# HV.net
KiCad netlist of a schematic drawn in Altium Designer
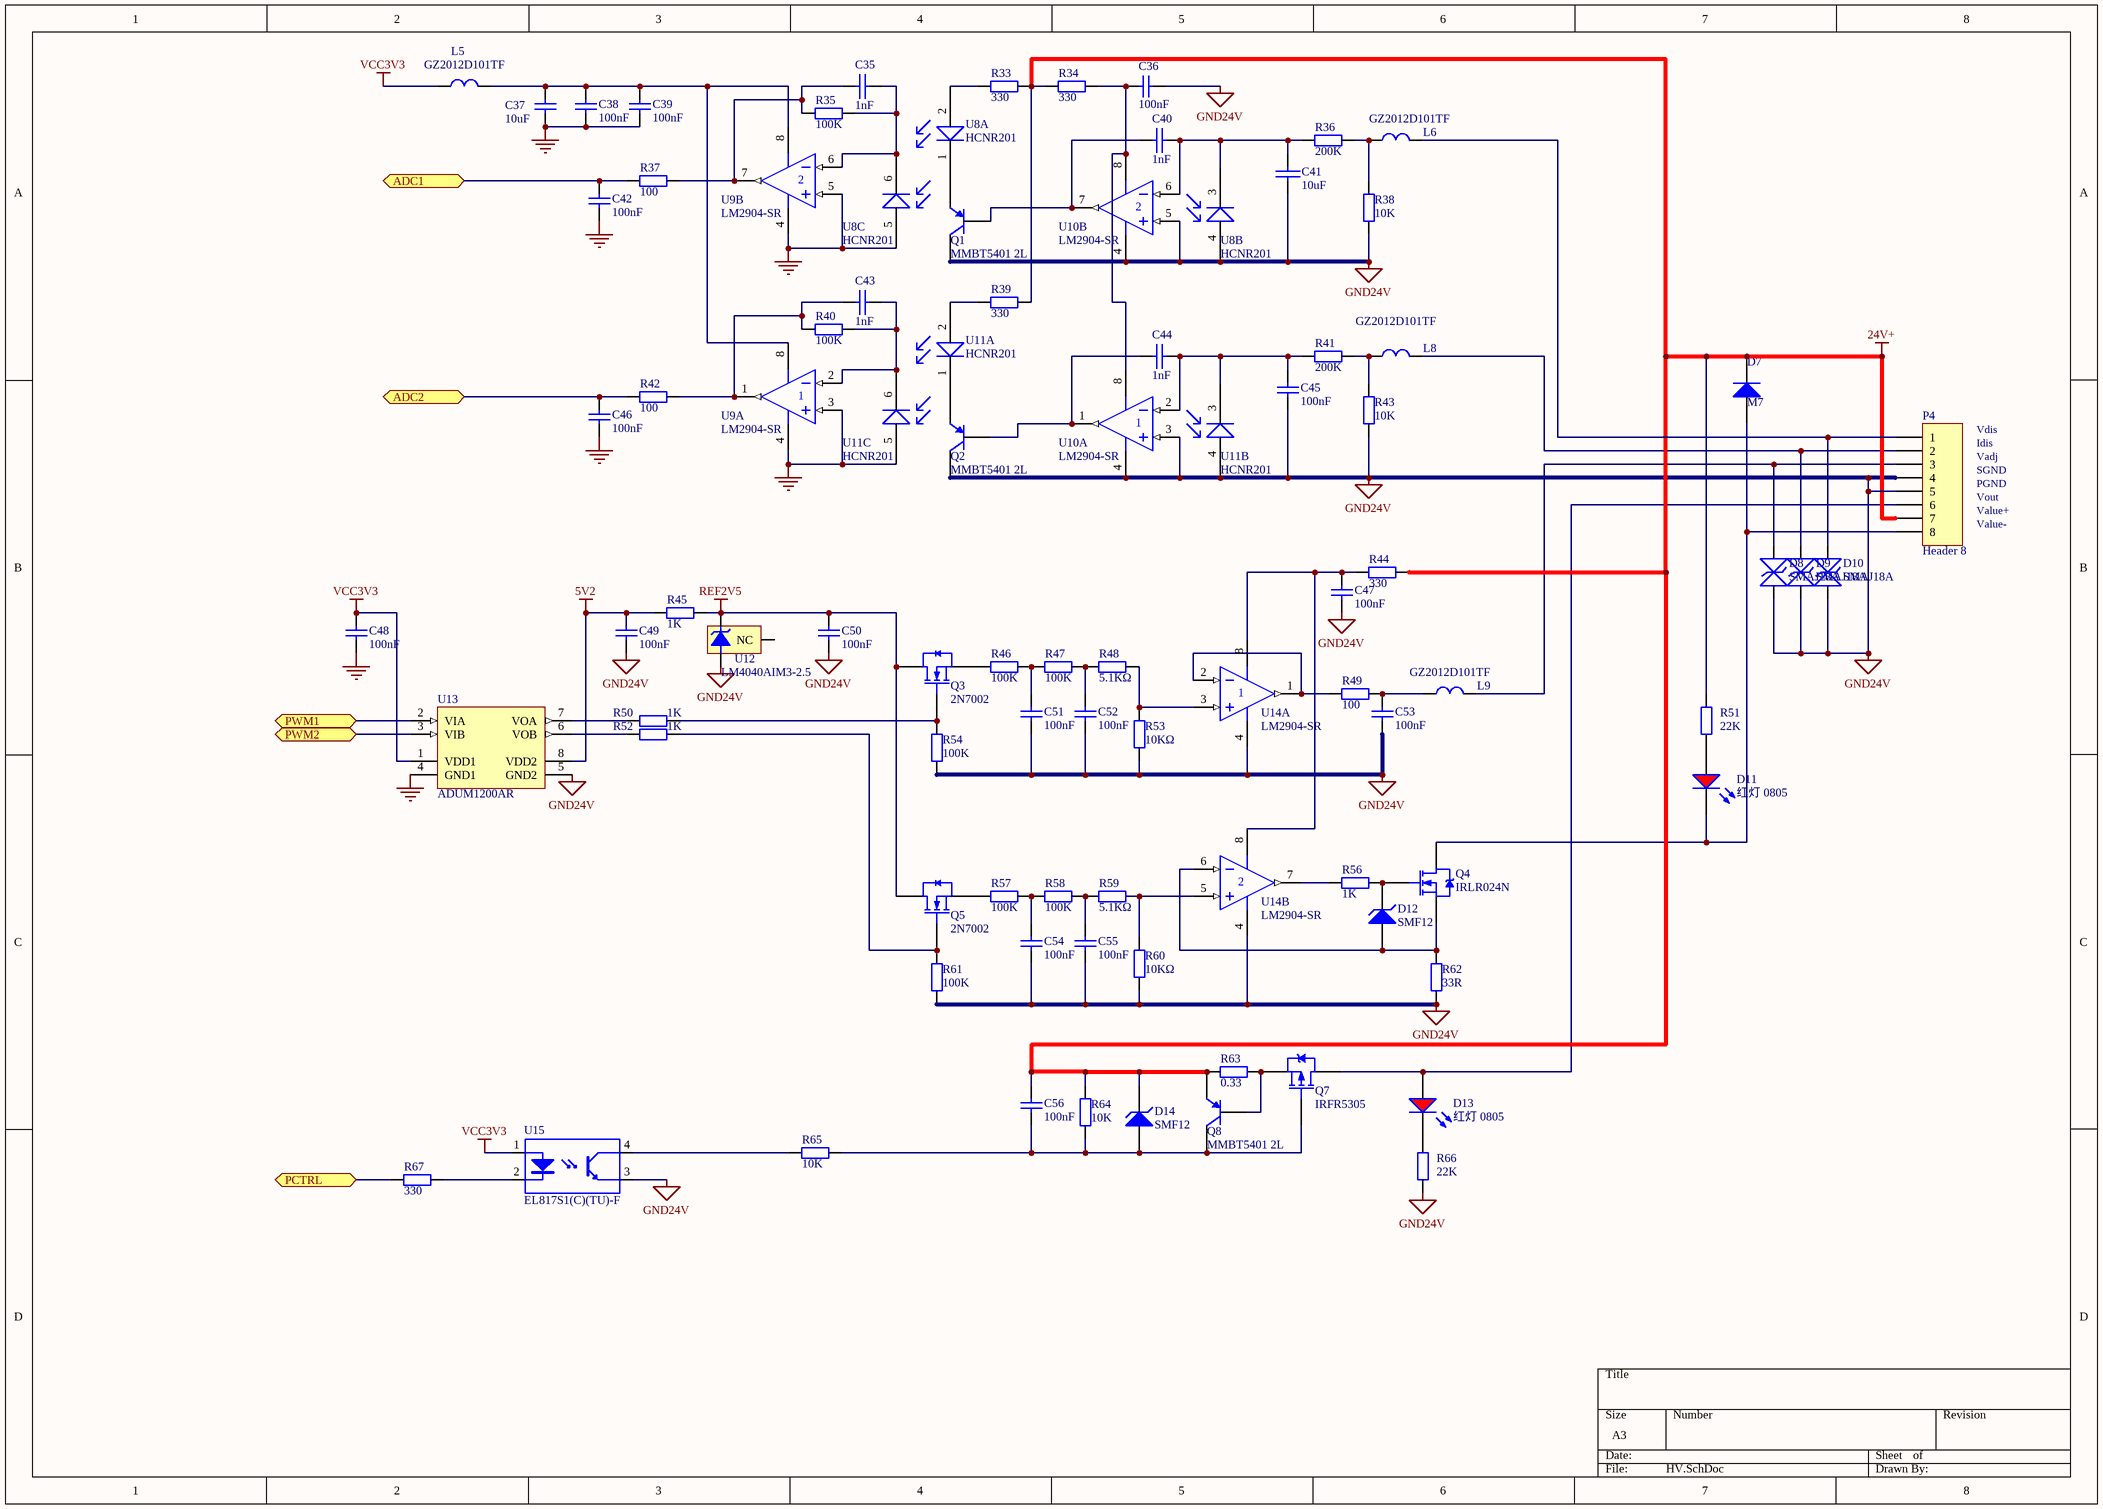
[diagram p0: HV.SchDoc]

(export (version "E")
  (design (tool "Eeschema 10.0.6"))
  (components
    (comp (ref "C35")
      (value "1nF")
      (footprint "0805_C")
      (description "Capacitor")
      (libsource (lib "*") (part "CAP"))
    )
    (comp (ref "C36")
      (value "100nF")
      (footprint "0805_C")
      (description "贴片电容")
      (libsource (lib "Miscellaneous Devices LC") (part "0805 100nF(104) 10% 50V"))
    )
    (comp (ref "C37")
      (value "10uF")
      (footprint "0805_C")
      (description "贴片电容")
      (libsource (lib "Miscellaneous Devices LC") (part "1206 10uF (106) 10% 50V"))
    )
    (comp (ref "C38")
      (value "100nF")
      (footprint "0805_C")
      (description "贴片电容")
      (libsource (lib "Miscellaneous Devices LC") (part "0805 100nF(104) 10% 50V"))
    )
    (comp (ref "C39")
      (value "100nF")
      (footprint "0805_C")
      (description "贴片电容")
      (libsource (lib "Miscellaneous Devices LC") (part "0805 100nF(104) 10% 50V"))
    )
    (comp (ref "C40")
      (value "1nF")
      (footprint "0805_C")
      (description "Capacitor")
      (libsource (lib "*") (part "CAP"))
    )
    (comp (ref "C41")
      (value "10uF")
      (footprint "0805_C")
      (description "Capacitor")
      (libsource (lib "*") (part "CC"))
    )
    (comp (ref "C42")
      (value "100nF")
      (footprint "0805_C")
      (description "贴片电容")
      (libsource (lib "Miscellaneous Devices LC") (part "0805 100nF(104) 10% 50V"))
    )
    (comp (ref "C43")
      (value "1nF")
      (footprint "0805_C")
      (description "Capacitor")
      (libsource (lib "*") (part "CAP"))
    )
    (comp (ref "C44")
      (value "1nF")
      (footprint "0805_C")
      (description "Capacitor")
      (libsource (lib "*") (part "CAP"))
    )
    (comp (ref "C45")
      (value "100nF")
      (footprint "0805_C")
      (description "贴片电容")
      (libsource (lib "Miscellaneous Devices LC") (part "0805 100nF(104) 10% 50V"))
    )
    (comp (ref "C46")
      (value "100nF")
      (footprint "0805_C")
      (description "贴片电容")
      (libsource (lib "Miscellaneous Devices LC") (part "0805 100nF(104) 10% 50V"))
    )
    (comp (ref "C47")
      (value "100nF")
      (footprint "0805_C")
      (description "贴片电容")
      (libsource (lib "Miscellaneous Devices LC") (part "0805 100nF(104) 10% 50V"))
    )
    (comp (ref "C48")
      (value "100nF")
      (footprint "0805_C")
      (description "贴片电容")
      (libsource (lib "Miscellaneous Devices LC") (part "0805 100nF(104) 10% 50V"))
    )
    (comp (ref "C49")
      (value "100nF")
      (footprint "0805_C")
      (description "贴片电容")
      (libsource (lib "Miscellaneous Devices LC") (part "0805 100nF(104) 10% 50V"))
    )
    (comp (ref "C50")
      (value "100nF")
      (footprint "0805_C")
      (description "贴片电容")
      (libsource (lib "Miscellaneous Devices LC") (part "0805 100nF(104) 10% 50V"))
    )
    (comp (ref "C51")
      (value "100nF")
      (footprint "0805_C")
      (description "贴片电容")
      (libsource (lib "Miscellaneous Devices LC") (part "0805 100nF(104) 10% 50V"))
    )
    (comp (ref "C52")
      (value "100nF")
      (footprint "0805_C")
      (description "贴片电容")
      (libsource (lib "Miscellaneous Devices LC") (part "0805 100nF(104) 10% 50V"))
    )
    (comp (ref "C53")
      (value "100nF")
      (footprint "0805_C")
      (description "贴片电容")
      (libsource (lib "Miscellaneous Devices LC") (part "0805 100nF(104) 10% 50V"))
    )
    (comp (ref "C54")
      (value "100nF")
      (footprint "0805_C")
      (description "贴片电容")
      (libsource (lib "Miscellaneous Devices LC") (part "0805 100nF(104) 10% 50V"))
    )
    (comp (ref "C55")
      (value "100nF")
      (footprint "0805_C")
      (description "贴片电容")
      (libsource (lib "Miscellaneous Devices LC") (part "0805 100nF(104) 10% 50V"))
    )
    (comp (ref "C56")
      (value "100nF")
      (footprint "0805_C")
      (description "贴片电容")
      (libsource (lib "Miscellaneous Devices LC") (part "0805 100nF(104) 10% 50V"))
    )
    (comp (ref "D7")
      (value "M7")
      (footprint "SMA(DO-214AC)_S1")
      (description "二极管")
      (libsource (lib "Miscellaneous Devices LC") (part "SMA(DO-214AC) M7"))
    )
    (comp (ref "D8") (value "SMAJ18A") (footprint "SMA") (libsource (lib "IC") (part "TVS")))
    (comp (ref "D9") (value "SMAJ18A") (footprint "SMA") (libsource (lib "IC") (part "TVS")))
    (comp (ref "D10") (value "SMAJ18A") (footprint "SMA") (libsource (lib "IC") (part "TVS")))
    (comp (ref "D11")
      (value "红灯 0805")
      (footprint "0805_LED_S1")
      (description "发光二极管")
      (libsource (lib "Miscellaneous Devices LC") (part "0805 红灯"))
    )
    (comp (ref "D12")
      (value "SMF12")
      (footprint "Miscellaneous Devices LC:SOD-123")
      (description "Zener Diode")
      (fields (field (name "PUBLISHER") "Altium Limited"))
      (libsource (lib "Miscellaneous Devices") (part "D Zener"))
    )
    (comp (ref "D13")
      (value "红灯 0805")
      (footprint "0805_LED_S1")
      (description "发光二极管")
      (libsource (lib "Miscellaneous Devices LC") (part "0805 红灯"))
    )
    (comp (ref "D14")
      (value "SMF12")
      (footprint "Miscellaneous Devices LC:SOD-123")
      (description "Zener Diode")
      (fields (field (name "PUBLISHER") "Altium Limited"))
      (libsource (lib "Miscellaneous Devices") (part "D Zener"))
    )
    (comp (ref "L5") (value "GZ2012D101TF") (footprint "0805_L") (libsource (lib "") (part "L1_1")))
    (comp (ref "L6") (value "GZ2012D101TF") (footprint "0805_L") (libsource (lib "") (part "L1_1")))
    (comp (ref "L8") (value "GZ2012D101TF") (footprint "0805_L") (libsource (lib "") (part "L1_1")))
    (comp (ref "L9") (value "GZ2012D101TF") (footprint "0805_L") (libsource (lib "Devices") (part "L1")))
    (comp (ref "P4")
      (value "Header 8")
      (footprint "MC1.5/8-ST-3.81")
      (description "Header, 8-Pin")
      (fields (field (name "PUBLISHER") "Altium Limited"))
      (libsource (lib "Miscellaneous Connectors") (part "Header 8"))
    )
    (comp (ref "Q1")
      (value "MMBT5401 2L")
      (footprint "SOT-23(SOT-23-3)")
      (description "三极管")
      (libsource (lib "Miscellaneous Devices LC") (part "SOT-23 MMBT5401 2L"))
    )
    (comp (ref "Q2")
      (value "MMBT5401 2L")
      (footprint "SOT-23(SOT-23-3)")
      (description "三极管")
      (libsource (lib "Miscellaneous Devices LC") (part "SOT-23 MMBT5401 2L"))
    )
    (comp (ref "Q3")
      (value "2N7002")
      (footprint "SOT-23(SOT-23-3)")
      (description "MOS(场效应管)")
      (libsource (lib "Miscellaneous Devices LC") (part "2N7002 7002"))
    )
    (comp (ref "Q4")
      (value "IRLR024N")
      (footprint "TO-252AA_N")
      (description "HEXFET Power MOSFET")
      (fields (field (name "PUBLISHER") "Altium Limited"))
      (libsource (lib "IR Discrete MOSFET - Power") (part "IRLR024N"))
    )
    (comp (ref "Q5")
      (value "2N7002")
      (footprint "SOT-23(SOT-23-3)")
      (description "MOS(场效应管)")
      (libsource (lib "Miscellaneous Devices LC") (part "2N7002 7002"))
    )
    (comp (ref "Q7")
      (value "IRFR5305")
      (footprint "TO-252AA_N")
      (description "HEXFET Power MOSFET")
      (fields (field (name "PUBLISHER") "Altium Limited"))
      (libsource (lib "IR Discrete MOSFET - Power") (part "IRFR5305"))
    )
    (comp (ref "Q8")
      (value "MMBT5401 2L")
      (footprint "SOT-23(SOT-23-3)")
      (description "三极管")
      (libsource (lib "Miscellaneous Devices LC") (part "SOT-23 MMBT5401 2L"))
    )
    (comp (ref "R33")
      (value "330")
      (footprint "0805_R")
      (description "Resistor")
      (fields (field (name "PUBLISHER") "Altium Limited"))
      (libsource (lib "") (part "Res2_2"))
    )
    (comp (ref "R34")
      (value "330")
      (footprint "0805_R")
      (description "Resistor")
      (fields (field (name "PUBLISHER") "Altium Limited"))
      (libsource (lib "") (part "Res2_2"))
    )
    (comp (ref "R35")
      (value "100K")
      (footprint "0805_R")
      (description "Resistor")
      (fields (field (name "PUBLISHER") "Altium Limited"))
      (libsource (lib "") (part "Res2_1"))
    )
    (comp (ref "R36")
      (value "200K")
      (footprint "0805_R")
      (description "Resistor")
      (fields (field (name "PUBLISHER") "Altium Limited"))
      (libsource (lib "") (part "Res2_1"))
    )
    (comp (ref "R37")
      (value "100")
      (footprint "0805_R")
      (description "Resistor")
      (fields (field (name "PUBLISHER") "Altium Limited"))
      (libsource (lib "") (part "Res2_2"))
    )
    (comp (ref "R38")
      (value "10K")
      (footprint "0805_R")
      (description "Resistor")
      (fields (field (name "PUBLISHER") "Altium Limited"))
      (libsource (lib "Miscellaneous Devices") (part "Res2"))
    )
    (comp (ref "R39")
      (value "330")
      (footprint "0805_R")
      (description "Resistor")
      (fields (field (name "PUBLISHER") "Altium Limited"))
      (libsource (lib "") (part "Res2_2"))
    )
    (comp (ref "R40")
      (value "100K")
      (footprint "0805_R")
      (description "Resistor")
      (fields (field (name "PUBLISHER") "Altium Limited"))
      (libsource (lib "") (part "Res2_1"))
    )
    (comp (ref "R41")
      (value "200K")
      (footprint "0805_R")
      (description "Resistor")
      (fields (field (name "PUBLISHER") "Altium Limited"))
      (libsource (lib "") (part "Res2_1"))
    )
    (comp (ref "R42")
      (value "100")
      (footprint "0805_R")
      (description "Resistor")
      (fields (field (name "PUBLISHER") "Altium Limited"))
      (libsource (lib "") (part "Res2_2"))
    )
    (comp (ref "R43")
      (value "10K")
      (footprint "0805_R")
      (description "Resistor")
      (fields (field (name "PUBLISHER") "Altium Limited"))
      (libsource (lib "Miscellaneous Devices") (part "Res2"))
    )
    (comp (ref "R44")
      (value "330")
      (footprint "0805_R")
      (description "贴片电阻")
      (libsource (lib "Miscellaneous Devices LC") (part "0805 100Ω (1000) 1%"))
    )
    (comp (ref "R45")
      (value "1K")
      (footprint "0805_R")
      (description "贴片电阻")
      (libsource (lib "Miscellaneous Devices LC") (part "0805 100KΩ (1003) 1%"))
    )
    (comp (ref "R46")
      (value "100K")
      (footprint "0805_R")
      (description "贴片电阻")
      (libsource (lib "Miscellaneous Devices LC") (part "0805 100KΩ (1003) 1%"))
    )
    (comp (ref "R47")
      (value "100K")
      (footprint "0805_R")
      (description "贴片电阻")
      (libsource (lib "Miscellaneous Devices LC") (part "0805 100KΩ (1003) 1%"))
    )
    (comp (ref "R48")
      (value "5.1KΩ")
      (footprint "0805_R")
      (description "贴片电阻")
      (libsource (lib "Miscellaneous Devices LC") (part "0805 5.1KΩ (5101) 1%"))
    )
    (comp (ref "R49")
      (value "100")
      (footprint "0805_R")
      (description "贴片电阻")
      (libsource (lib "Miscellaneous Devices LC") (part "0805 100KΩ (1003) 1%"))
    )
    (comp (ref "R50")
      (value "1K")
      (footprint "0805_R")
      (description "贴片电阻")
      (libsource (lib "") (part "0805 100KΩ (1003) 1%_1"))
    )
    (comp (ref "R51")
      (value "22K")
      (footprint "R0805")
      (description "贴片电阻")
      (libsource (lib "电阻") (part "RMK2012KBxxx（10～1M）F"))
    )
    (comp (ref "R52")
      (value "1K")
      (footprint "0805_R")
      (description "贴片电阻")
      (libsource (lib "") (part "0805 100KΩ (1003) 1%_1"))
    )
    (comp (ref "R53")
      (value "10KΩ")
      (footprint "0805_R")
      (description "贴片电阻")
      (libsource (lib "Miscellaneous Devices LC") (part "0805 10KΩ (1002) 1%"))
    )
    (comp (ref "R54")
      (value "100K")
      (footprint "0805_R")
      (description "贴片电阻")
      (libsource (lib "") (part "0805 100KΩ (1003) 1%_2"))
    )
    (comp (ref "R56")
      (value "1K")
      (footprint "0805_R")
      (description "贴片电阻")
      (libsource (lib "Miscellaneous Devices LC") (part "0805 100KΩ (1003) 1%"))
    )
    (comp (ref "R57")
      (value "100K")
      (footprint "0805_R")
      (description "贴片电阻")
      (libsource (lib "Miscellaneous Devices LC") (part "0805 100KΩ (1003) 1%"))
    )
    (comp (ref "R58")
      (value "100K")
      (footprint "0805_R")
      (description "贴片电阻")
      (libsource (lib "Miscellaneous Devices LC") (part "0805 100KΩ (1003) 1%"))
    )
    (comp (ref "R59")
      (value "5.1KΩ")
      (footprint "0805_R")
      (description "贴片电阻")
      (libsource (lib "Miscellaneous Devices LC") (part "0805 5.1KΩ (5101) 1%"))
    )
    (comp (ref "R60")
      (value "10KΩ")
      (footprint "0805_R")
      (description "贴片电阻")
      (libsource (lib "Miscellaneous Devices LC") (part "0805 10KΩ (1002) 1%"))
    )
    (comp (ref "R61")
      (value "100K")
      (footprint "0805_R")
      (description "贴片电阻")
      (libsource (lib "") (part "0805 100KΩ (1003) 1%_2"))
    )
    (comp (ref "R62")
      (value "33R")
      (footprint "R2512")
      (description "Resistor")
      (fields (field (name "PUBLISHER") "Altium Limited"))
      (libsource (lib "") (part "Res2_3"))
    )
    (comp (ref "R63")
      (value "0.33")
      (footprint "R2512")
      (description "Resistor")
      (fields (field (name "PUBLISHER") "Altium Limited"))
      (libsource (lib "") (part "Res2_4"))
    )
    (comp (ref "R64")
      (value "10K")
      (footprint "0805_R")
      (description "Resistor")
      (fields (field (name "PUBLISHER") "Altium Limited"))
      (libsource (lib "") (part "Res2_3"))
    )
    (comp (ref "R65")
      (value "10K")
      (footprint "0805_R")
      (description "Resistor")
      (fields (field (name "PUBLISHER") "Altium Limited"))
      (libsource (lib "") (part "Res2_4"))
    )
    (comp (ref "R66")
      (value "22K")
      (footprint "0805_R")
      (description "贴片电阻")
      (libsource (lib "电阻") (part "RMK2012KBxxx（10～1M）F"))
    )
    (comp (ref "R67")
      (value "330")
      (footprint "0805_R")
      (description "Resistor")
      (fields (field (name "PUBLISHER") "Altium Limited"))
      (libsource (lib "") (part "Res2_5"))
    )
    (comp (ref "U8") (value "HCNR201") (footprint "SMD-8_9.0mm") (libsource (lib "*") (part "HCNR201")))
    (comp (ref "U9")
      (value "LM2904-SR")
      (footprint "SOIC-8_150mil")
      (description "Dual Low-Power Operational Amplifier")
      (fields (field (name "PUBLISHER") "Altium Limited"))
      (libsource (lib "Miscellaneous Devices LC") (part "LM2904D"))
    )
    (comp (ref "U10")
      (value "LM2904-SR")
      (footprint "SOIC-8_150mil")
      (description "Dual Low-Power Operational Amplifier")
      (fields (field (name "PUBLISHER") "Altium Limited"))
      (libsource (lib "Miscellaneous Devices LC") (part "LM2904D"))
    )
    (comp (ref "U11") (value "HCNR201") (footprint "SMD-8_9.0mm") (libsource (lib "*") (part "HCNR201")))
    (comp (ref "U12")
      (value "LM4040AIM3-2.5")
      (footprint "MF03A_N")
      (description "Precision Micropower Shunt Voltage Reference, 3-pin SOT-23")
      (fields (field (name "MANUFACTURER") "National Semiconductor"))
      (libsource (lib "National Semiconductor Voltage Reference") (part "LM4040AIM3-2.5"))
    )
    (comp (ref "U13")
      (value "ADUM1200AR")
      (footprint "ADI-R-8_N")
      (fields (field (name "MANUFACTURER") "Analog Devices"))
      (libsource (lib "Analog Devices Interface and Isolation Digital Isolators") (part "ADUM1200AR"))
    )
    (comp (ref "U14")
      (value "LM2904-SR")
      (footprint "SOIC-8_150mil")
      (description "Dual Low-Power Operational Amplifier")
      (fields (field (name "PUBLISHER") "Altium Limited"))
      (libsource (lib "Miscellaneous Devices LC") (part "LM2904D"))
    )
    (comp (ref "U15")
      (value "EL817S1(C)(TU)-F")
      (footprint "LC-SMD-4")
      (libsource (lib "IC") (part "TLP521"))
    )
  )
  (nets
    (net (code "1") (name "/ADC1") (class "Default")
      (node (ref "C42") (pin "2") (pinfunction "2_2") (pintype "passive"))
      (node (ref "R37") (pin "2") (pinfunction "2_2") (pintype "passive"))
    )
    (net (code "2") (name "/ADC2") (class "Default")
      (node (ref "C46") (pin "2") (pinfunction "2_2") (pintype "passive"))
      (node (ref "R42") (pin "2") (pinfunction "2_2") (pintype "passive"))
    )
    (net (code "3") (name "/PCTRL") (class "Default")
      (node (ref "R67") (pin "1") (pinfunction "1_1") (pintype "passive"))
    )
    (net (code "4") (name "/PWM1") (class "Default")
      (node (ref "U13") (pin "2") (pinfunction "VIA_2") (pintype "input"))
    )
    (net (code "5") (name "/PWM2") (class "Default")
      (node (ref "U13") (pin "3") (pinfunction "VIB_3") (pintype "input"))
    )
    (net (code "6") (name "5V2") (class "Default")
      (node (ref "C49") (pin "2") (pinfunction "2_2") (pintype "passive"))
      (node (ref "R45") (pin "2") (pinfunction "2_2") (pintype "passive"))
      (node (ref "U13") (pin "8") (pinfunction "VDD2_8") (pintype "power_in"))
    )
    (net (code "7") (name "24V+") (class "Default")
      (node (ref "C56") (pin "2") (pinfunction "2_2") (pintype "passive"))
      (node (ref "D14") (pin "2") (pinfunction "K_2") (pintype "passive"))
      (node (ref "D7") (pin "2") (pinfunction "K_2") (pintype "passive"))
      (node (ref "P4") (pin "7") (pinfunction "7_7") (pintype "passive"))
      (node (ref "Q8") (pin "2") (pinfunction "E_2") (pintype "passive"))
      (node (ref "R33") (pin "1") (pinfunction "1_1") (pintype "passive"))
      (node (ref "R34") (pin "2") (pinfunction "2_2") (pintype "passive"))
      (node (ref "R39") (pin "1") (pinfunction "1_1") (pintype "passive"))
      (node (ref "R44") (pin "1") (pinfunction "1_1") (pintype "passive"))
      (node (ref "R51") (pin "1") (pinfunction "1_1") (pintype "passive"))
      (node (ref "R63") (pin "2") (pinfunction "2_2") (pintype "passive"))
      (node (ref "R64") (pin "2") (pinfunction "2_2") (pintype "passive"))
    )
    (net (code "8") (name "GND") (class "Default")
      (node (ref "C37") (pin "1") (pinfunction "1_1") (pintype "passive"))
      (node (ref "C38") (pin "1") (pinfunction "1_1") (pintype "passive"))
      (node (ref "C39") (pin "1") (pinfunction "1_1") (pintype "passive"))
      (node (ref "C42") (pin "1") (pinfunction "1_1") (pintype "passive"))
      (node (ref "C46") (pin "1") (pinfunction "1_1") (pintype "passive"))
      (node (ref "C48") (pin "1") (pinfunction "1_1") (pintype "passive"))
      (node (ref "U11") (pin "5") (pinfunction "+_5") (pintype "passive"))
      (node (ref "U13") (pin "4") (pinfunction "GND1_4") (pintype "power_in"))
      (node (ref "U8") (pin "5") (pinfunction "+_5") (pintype "passive"))
      (node (ref "U9") (pin "3") (pinfunction "IN+_3") (pintype "input"))
      (node (ref "U9") (pin "4") (pinfunction "V-_4") (pintype "power_in"))
      (node (ref "U9") (pin "5") (pinfunction "IN+_5") (pintype "input"))
    )
    (net (code "9") (name "GND24V") (class "Default")
      (node (ref "C36") (pin "1") (pinfunction "1_1") (pintype "passive"))
      (node (ref "C41") (pin "1") (pinfunction "1_1") (pintype "passive"))
      (node (ref "C45") (pin "1") (pinfunction "1_1") (pintype "passive"))
      (node (ref "C47") (pin "1") (pinfunction "1_1") (pintype "passive"))
      (node (ref "C49") (pin "1") (pinfunction "1_1") (pintype "passive"))
      (node (ref "C50") (pin "1") (pinfunction "1_1") (pintype "passive"))
      (node (ref "C51") (pin "1") (pinfunction "1_1") (pintype "passive"))
      (node (ref "C52") (pin "1") (pinfunction "1_1") (pintype "passive"))
      (node (ref "C53") (pin "1") (pinfunction "1_1") (pintype "passive"))
      (node (ref "C54") (pin "1") (pinfunction "1_1") (pintype "passive"))
      (node (ref "C55") (pin "1") (pinfunction "1_1") (pintype "passive"))
      (node (ref "D10") (pin "1") (pinfunction "1_1") (pintype "passive"))
      (node (ref "D8") (pin "1") (pinfunction "1_1") (pintype "passive"))
      (node (ref "D9") (pin "1") (pinfunction "1_1") (pintype "passive"))
      (node (ref "P4") (pin "4") (pinfunction "4_4") (pintype "passive"))
      (node (ref "P4") (pin "5") (pinfunction "5_5") (pintype "passive"))
      (node (ref "Q1") (pin "3") (pinfunction "C_3") (pintype "passive"))
      (node (ref "Q2") (pin "3") (pinfunction "C_3") (pintype "passive"))
      (node (ref "R38") (pin "1") (pinfunction "1_1") (pintype "passive"))
      (node (ref "R43") (pin "1") (pinfunction "1_1") (pintype "passive"))
      (node (ref "R53") (pin "2") (pinfunction "2_2") (pintype "passive"))
      (node (ref "R54") (pin "2") (pinfunction "2_2") (pintype "passive"))
      (node (ref "R60") (pin "2") (pinfunction "2_2") (pintype "passive"))
      (node (ref "R61") (pin "2") (pinfunction "2_2") (pintype "passive"))
      (node (ref "R62") (pin "1") (pinfunction "1_1") (pintype "passive"))
      (node (ref "R66") (pin "2") (pinfunction "2_2") (pintype "passive"))
      (node (ref "U10") (pin "3") (pinfunction "IN+_3") (pintype "input"))
      (node (ref "U10") (pin "4") (pinfunction "V-_4") (pintype "power_in"))
      (node (ref "U10") (pin "5") (pinfunction "IN+_5") (pintype "input"))
      (node (ref "U11") (pin "4") (pinfunction "+_4") (pintype "passive"))
      (node (ref "U12") (pin "2") (pinfunction "-V_2") (pintype "passive"))
      (node (ref "U13") (pin "5") (pinfunction "GND2_5") (pintype "power_in"))
      (node (ref "U14") (pin "4") (pinfunction "V-_4") (pintype "power_in"))
      (node (ref "U15") (pin "3") (pinfunction "E_3") (pintype "passive"))
      (node (ref "U8") (pin "4") (pinfunction "+_4") (pintype "passive"))
    )
    (net (code "10") (name "Net-(C51-Pad2)") (class "Default")
      (node (ref "C51") (pin "2") (pinfunction "2_2") (pintype "passive"))
      (node (ref "R46") (pin "1") (pinfunction "1_1") (pintype "passive"))
      (node (ref "R47") (pin "2") (pinfunction "2_2") (pintype "passive"))
    )
    (net (code "11") (name "Net-(C52-Pad2)") (class "Default")
      (node (ref "C52") (pin "2") (pinfunction "2_2") (pintype "passive"))
      (node (ref "R47") (pin "1") (pinfunction "1_1") (pintype "passive"))
      (node (ref "R48") (pin "2") (pinfunction "2_2") (pintype "passive"))
    )
    (net (code "12") (name "Net-(C53-Pad2)") (class "Default")
      (node (ref "C53") (pin "2") (pinfunction "2_2") (pintype "passive"))
      (node (ref "L9") (pin "2") (pinfunction "2_2") (pintype "passive"))
      (node (ref "R49") (pin "1") (pinfunction "1_1") (pintype "passive"))
    )
    (net (code "13") (name "Net-(C54-Pad2)") (class "Default")
      (node (ref "C54") (pin "2") (pinfunction "2_2") (pintype "passive"))
      (node (ref "R57") (pin "1") (pinfunction "1_1") (pintype "passive"))
      (node (ref "R58") (pin "2") (pinfunction "2_2") (pintype "passive"))
    )
    (net (code "14") (name "Net-(C55-Pad2)") (class "Default")
      (node (ref "C55") (pin "2") (pinfunction "2_2") (pintype "passive"))
      (node (ref "R58") (pin "1") (pinfunction "1_1") (pintype "passive"))
      (node (ref "R59") (pin "2") (pinfunction "2_2") (pintype "passive"))
    )
    (net (code "15") (name "Net-(D7-A)") (class "Default")
      (node (ref "D11") (pin "K") (pinfunction "K_K") (pintype "passive"))
      (node (ref "D7") (pin "1") (pinfunction "A_1") (pintype "passive"))
      (node (ref "P4") (pin "8") (pinfunction "8_8") (pintype "passive"))
      (node (ref "Q4") (pin "4") (pinfunction "D_4") (pintype "passive"))
    )
    (net (code "16") (name "Net-(D8-Pad2)") (class "Default")
      (node (ref "D8") (pin "2") (pinfunction "2_2") (pintype "passive"))
      (node (ref "L9") (pin "1") (pinfunction "1_1") (pintype "passive"))
      (node (ref "P4") (pin "3") (pinfunction "3_3") (pintype "passive"))
    )
    (net (code "17") (name "Net-(D9-Pad2)") (class "Default")
      (node (ref "D9") (pin "2") (pinfunction "2_2") (pintype "passive"))
      (node (ref "L8") (pin "2") (pinfunction "2_2") (pintype "passive"))
      (node (ref "P4") (pin "2") (pinfunction "2_2") (pintype "passive"))
    )
    (net (code "18") (name "Net-(D10-Pad2)") (class "Default")
      (node (ref "D10") (pin "2") (pinfunction "2_2") (pintype "passive"))
      (node (ref "L6") (pin "2") (pinfunction "2_2") (pintype "passive"))
      (node (ref "P4") (pin "1") (pinfunction "1_1") (pintype "passive"))
    )
    (net (code "19") (name "Net-(D11-PadA)") (class "Default")
      (node (ref "D11") (pin "A") (pinfunction "A_A") (pintype "passive"))
      (node (ref "R51") (pin "2") (pinfunction "2_2") (pintype "passive"))
    )
    (net (code "20") (name "Net-(D12-A)") (class "Default")
      (node (ref "D12") (pin "1") (pinfunction "A_1") (pintype "passive"))
      (node (ref "Q4") (pin "3") (pinfunction "S_3") (pintype "passive"))
      (node (ref "R62") (pin "2") (pinfunction "2_2") (pintype "passive"))
      (node (ref "U14") (pin "6") (pinfunction "IN-_6") (pintype "input"))
    )
    (net (code "21") (name "Net-(D12-K)") (class "Default")
      (node (ref "D12") (pin "2") (pinfunction "K_2") (pintype "passive"))
      (node (ref "Q4") (pin "1") (pinfunction "G_1") (pintype "passive"))
      (node (ref "R56") (pin "1") (pinfunction "1_1") (pintype "passive"))
    )
    (net (code "22") (name "Net-(D13-PadK)") (class "Default")
      (node (ref "D13") (pin "K") (pinfunction "K_K") (pintype "passive"))
      (node (ref "R66") (pin "1") (pinfunction "1_1") (pintype "passive"))
    )
    (net (code "23") (name "Net-(D14-A)") (class "Default")
      (node (ref "C56") (pin "1") (pinfunction "1_1") (pintype "passive"))
      (node (ref "D14") (pin "1") (pinfunction "A_1") (pintype "passive"))
      (node (ref "Q7") (pin "1") (pinfunction "G_1") (pintype "passive"))
      (node (ref "Q8") (pin "3") (pinfunction "C_3") (pintype "passive"))
      (node (ref "R64") (pin "1") (pinfunction "1_1") (pintype "passive"))
      (node (ref "R65") (pin "1") (pinfunction "1_1") (pintype "passive"))
    )
    (net (code "24") (name "Net-(L6-Pad1)") (class "Default")
      (node (ref "L6") (pin "1") (pinfunction "1_1") (pintype "passive"))
      (node (ref "R36") (pin "2") (pinfunction "2_2") (pintype "passive"))
      (node (ref "R38") (pin "2") (pinfunction "2_2") (pintype "passive"))
    )
    (net (code "25") (name "Net-(L8-Pad1)") (class "Default")
      (node (ref "L8") (pin "1") (pinfunction "1_1") (pintype "passive"))
      (node (ref "R41") (pin "2") (pinfunction "2_2") (pintype "passive"))
      (node (ref "R43") (pin "2") (pinfunction "2_2") (pintype "passive"))
    )
    (net (code "26") (name "Net-(Q1-B)") (class "Default")
      (node (ref "C40") (pin "2") (pinfunction "2_2") (pintype "passive"))
      (node (ref "Q1") (pin "1") (pinfunction "B_1") (pintype "passive"))
      (node (ref "U10") (pin "7") (pinfunction "OUT_7") (pintype "output"))
    )
    (net (code "27") (name "Net-(Q1-E)") (class "Default")
      (node (ref "Q1") (pin "2") (pinfunction "E_2") (pintype "passive"))
      (node (ref "U8") (pin "1") (pinfunction "-_1") (pintype "passive"))
    )
    (net (code "28") (name "Net-(Q2-B)") (class "Default")
      (node (ref "C44") (pin "2") (pinfunction "2_2") (pintype "passive"))
      (node (ref "Q2") (pin "1") (pinfunction "B_1") (pintype "passive"))
      (node (ref "U10") (pin "1") (pinfunction "OUT_1") (pintype "output"))
    )
    (net (code "29") (name "Net-(Q2-E)") (class "Default")
      (node (ref "Q2") (pin "2") (pinfunction "E_2") (pintype "passive"))
      (node (ref "U11") (pin "1") (pinfunction "-_1") (pintype "passive"))
    )
    (net (code "30") (name "Net-(Q3-G)") (class "Default")
      (node (ref "Q3") (pin "1") (pinfunction "G_1") (pintype "passive"))
      (node (ref "R50") (pin "2") (pinfunction "2_2") (pintype "passive"))
      (node (ref "R54") (pin "1") (pinfunction "1_1") (pintype "passive"))
    )
    (net (code "31") (name "Net-(Q3-S)") (class "Default")
      (node (ref "Q3") (pin "2") (pinfunction "S_2") (pintype "passive"))
      (node (ref "R46") (pin "2") (pinfunction "2_2") (pintype "passive"))
    )
    (net (code "32") (name "Net-(Q5-G)") (class "Default")
      (node (ref "Q5") (pin "1") (pinfunction "G_1") (pintype "passive"))
      (node (ref "R52") (pin "2") (pinfunction "2_2") (pintype "passive"))
      (node (ref "R61") (pin "1") (pinfunction "1_1") (pintype "passive"))
    )
    (net (code "33") (name "Net-(Q5-S)") (class "Default")
      (node (ref "Q5") (pin "2") (pinfunction "S_2") (pintype "passive"))
      (node (ref "R57") (pin "2") (pinfunction "2_2") (pintype "passive"))
    )
    (net (code "34") (name "Net-(Q7-D)") (class "Default")
      (node (ref "D13") (pin "A") (pinfunction "A_A") (pintype "passive"))
      (node (ref "P4") (pin "6") (pinfunction "6_6") (pintype "passive"))
      (node (ref "Q7") (pin "4") (pinfunction "D_4") (pintype "passive"))
    )
    (net (code "35") (name "Net-(Q7-S)") (class "Default")
      (node (ref "Q7") (pin "3") (pinfunction "S_3") (pintype "passive"))
      (node (ref "Q8") (pin "1") (pinfunction "B_1") (pintype "passive"))
      (node (ref "R63") (pin "1") (pinfunction "1_1") (pintype "passive"))
    )
    (net (code "36") (name "Net-(U8A-+)") (class "Default")
      (node (ref "R33") (pin "2") (pinfunction "2_2") (pintype "passive"))
      (node (ref "U8") (pin "2") (pinfunction "+_2") (pintype "passive"))
    )
    (net (code "37") (name "Net-(U8C--)") (class "Default")
      (node (ref "C35") (pin "1") (pinfunction "1_1") (pintype "passive"))
      (node (ref "R35") (pin "2") (pinfunction "2_2") (pintype "passive"))
      (node (ref "U8") (pin "6") (pinfunction "-_6") (pintype "passive"))
      (node (ref "U9") (pin "6") (pinfunction "IN-_6") (pintype "input"))
    )
    (net (code "38") (name "Net-(U9A-OUT)") (class "Default")
      (node (ref "C43") (pin "2") (pinfunction "2_2") (pintype "passive"))
      (node (ref "R40") (pin "1") (pinfunction "1_1") (pintype "passive"))
      (node (ref "R42") (pin "1") (pinfunction "1_1") (pintype "passive"))
      (node (ref "U9") (pin "1") (pinfunction "OUT_1") (pintype "output"))
    )
    (net (code "39") (name "Net-(U9A-V+)") (class "Default")
      (node (ref "C37") (pin "2") (pinfunction "2_2") (pintype "passive"))
      (node (ref "C38") (pin "2") (pinfunction "2_2") (pintype "passive"))
      (node (ref "C39") (pin "2") (pinfunction "2_2") (pintype "passive"))
      (node (ref "L5") (pin "2") (pinfunction "2_2") (pintype "passive"))
      (node (ref "U9") (pin "8") (pinfunction "V+_8") (pintype "power_in"))
    )
    (net (code "40") (name "Net-(U9B-OUT)") (class "Default")
      (node (ref "C35") (pin "2") (pinfunction "2_2") (pintype "passive"))
      (node (ref "R35") (pin "1") (pinfunction "1_1") (pintype "passive"))
      (node (ref "R37") (pin "1") (pinfunction "1_1") (pintype "passive"))
      (node (ref "U9") (pin "7") (pinfunction "OUT_7") (pintype "output"))
    )
    (net (code "41") (name "Net-(U10A-IN-)") (class "Default")
      (node (ref "C44") (pin "1") (pinfunction "1_1") (pintype "passive"))
      (node (ref "C45") (pin "2") (pinfunction "2_2") (pintype "passive"))
      (node (ref "R41") (pin "1") (pinfunction "1_1") (pintype "passive"))
      (node (ref "U10") (pin "2") (pinfunction "IN-_2") (pintype "input"))
      (node (ref "U11") (pin "3") (pinfunction "-_3") (pintype "passive"))
    )
    (net (code "42") (name "Net-(U10A-V+)") (class "Default")
      (node (ref "C36") (pin "2") (pinfunction "2_2") (pintype "passive"))
      (node (ref "R34") (pin "1") (pinfunction "1_1") (pintype "passive"))
      (node (ref "U10") (pin "8") (pinfunction "V+_8") (pintype "power_in"))
    )
    (net (code "43") (name "Net-(U10B-IN-)") (class "Default")
      (node (ref "C40") (pin "1") (pinfunction "1_1") (pintype "passive"))
      (node (ref "C41") (pin "2") (pinfunction "2_2") (pintype "passive"))
      (node (ref "R36") (pin "1") (pinfunction "1_1") (pintype "passive"))
      (node (ref "U10") (pin "6") (pinfunction "IN-_6") (pintype "input"))
      (node (ref "U8") (pin "3") (pinfunction "-_3") (pintype "passive"))
    )
    (net (code "44") (name "Net-(U11A-+)") (class "Default")
      (node (ref "R39") (pin "2") (pinfunction "2_2") (pintype "passive"))
      (node (ref "U11") (pin "2") (pinfunction "+_2") (pintype "passive"))
    )
    (net (code "45") (name "Net-(U11C--)") (class "Default")
      (node (ref "C43") (pin "1") (pinfunction "1_1") (pintype "passive"))
      (node (ref "R40") (pin "2") (pinfunction "2_2") (pintype "passive"))
      (node (ref "U11") (pin "6") (pinfunction "-_6") (pintype "passive"))
      (node (ref "U9") (pin "2") (pinfunction "IN-_2") (pintype "input"))
    )
    (net (code "46") (name "Net-(U13-VOA)") (class "Default")
      (node (ref "R50") (pin "1") (pinfunction "1_1") (pintype "passive"))
      (node (ref "U13") (pin "7") (pinfunction "VOA_7") (pintype "output"))
    )
    (net (code "47") (name "Net-(U13-VOB)") (class "Default")
      (node (ref "R52") (pin "1") (pinfunction "1_1") (pintype "passive"))
      (node (ref "U13") (pin "6") (pinfunction "VOB_6") (pintype "output"))
    )
    (net (code "48") (name "Net-(U14A-IN+)") (class "Default")
      (node (ref "R48") (pin "1") (pinfunction "1_1") (pintype "passive"))
      (node (ref "R53") (pin "1") (pinfunction "1_1") (pintype "passive"))
      (node (ref "U14") (pin "3") (pinfunction "IN+_3") (pintype "input"))
    )
    (net (code "49") (name "Net-(U14A-IN-)") (class "Default")
      (node (ref "R49") (pin "2") (pinfunction "2_2") (pintype "passive"))
      (node (ref "U14") (pin "1") (pinfunction "OUT_1") (pintype "output"))
      (node (ref "U14") (pin "2") (pinfunction "IN-_2") (pintype "input"))
    )
    (net (code "50") (name "Net-(U14A-V+)") (class "Default")
      (node (ref "C47") (pin "2") (pinfunction "2_2") (pintype "passive"))
      (node (ref "R44") (pin "2") (pinfunction "2_2") (pintype "passive"))
      (node (ref "U14") (pin "8") (pinfunction "V+_8") (pintype "power_in"))
    )
    (net (code "51") (name "Net-(U14B-IN+)") (class "Default")
      (node (ref "R59") (pin "1") (pinfunction "1_1") (pintype "passive"))
      (node (ref "R60") (pin "1") (pinfunction "1_1") (pintype "passive"))
      (node (ref "U14") (pin "5") (pinfunction "IN+_5") (pintype "input"))
    )
    (net (code "52") (name "Net-(U14B-OUT)") (class "Default")
      (node (ref "R56") (pin "2") (pinfunction "2_2") (pintype "passive"))
      (node (ref "U14") (pin "7") (pinfunction "OUT_7") (pintype "output"))
    )
    (net (code "53") (name "Net-(U15-C)") (class "Default")
      (node (ref "R65") (pin "2") (pinfunction "2_2") (pintype "passive"))
      (node (ref "U15") (pin "4") (pinfunction "C_4") (pintype "passive"))
    )
    (net (code "54") (name "Net-(U15-K)") (class "Default")
      (node (ref "R67") (pin "2") (pinfunction "2_2") (pintype "passive"))
      (node (ref "U15") (pin "2") (pinfunction "K_2") (pintype "passive"))
    )
    (net (code "55") (name "REF2V5") (class "Default")
      (node (ref "C50") (pin "2") (pinfunction "2_2") (pintype "passive"))
      (node (ref "Q3") (pin "3") (pinfunction "D_3") (pintype "passive"))
      (node (ref "Q5") (pin "3") (pinfunction "D_3") (pintype "passive"))
      (node (ref "R45") (pin "1") (pinfunction "1_1") (pintype "passive"))
      (node (ref "U12") (pin "1") (pinfunction "+V_1") (pintype "passive"))
    )
    (net (code "56") (name "VCC3V3") (class "Default")
      (node (ref "C48") (pin "2") (pinfunction "2_2") (pintype "passive"))
      (node (ref "L5") (pin "1") (pinfunction "1_1") (pintype "passive"))
      (node (ref "U13") (pin "1") (pinfunction "VDD1_1") (pintype "power_in"))
      (node (ref "U15") (pin "1") (pinfunction "A_1") (pintype "passive"))
    )
    (net (code "57") (name "unconnected-(U12-NC-Pad3)") (class "Default")
      (node (ref "U12") (pin "3") (pinfunction "NC_3") (pintype "passive"))
    )
  )
)
